# SensorBoard2.net
KiCad netlist of a schematic drawn in EAGLE
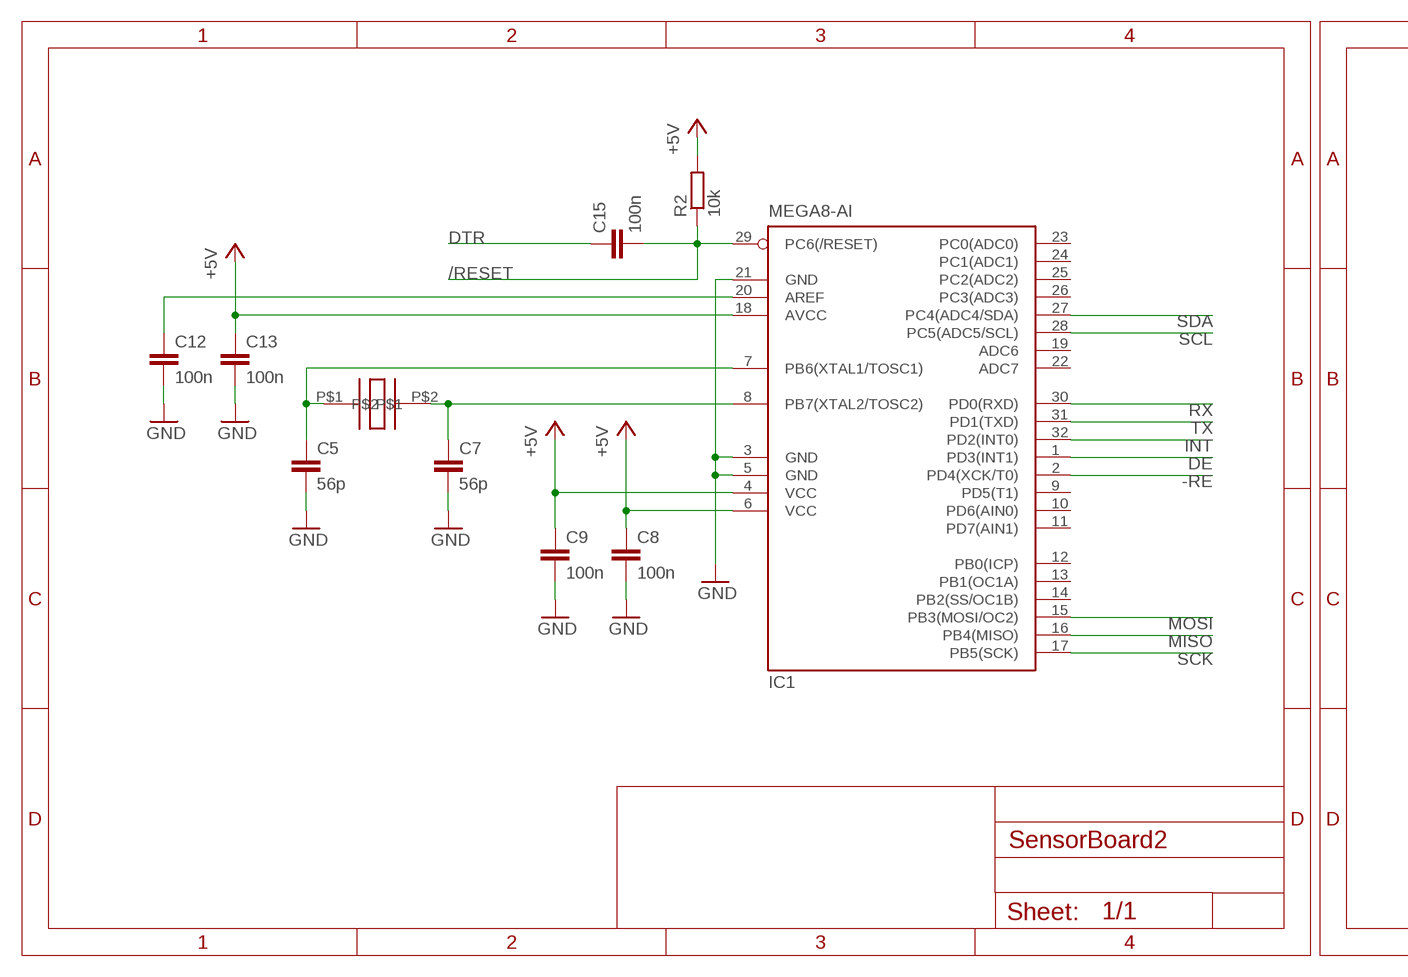
[diagram p0: schematic, sheet 1, part 1 of 2]
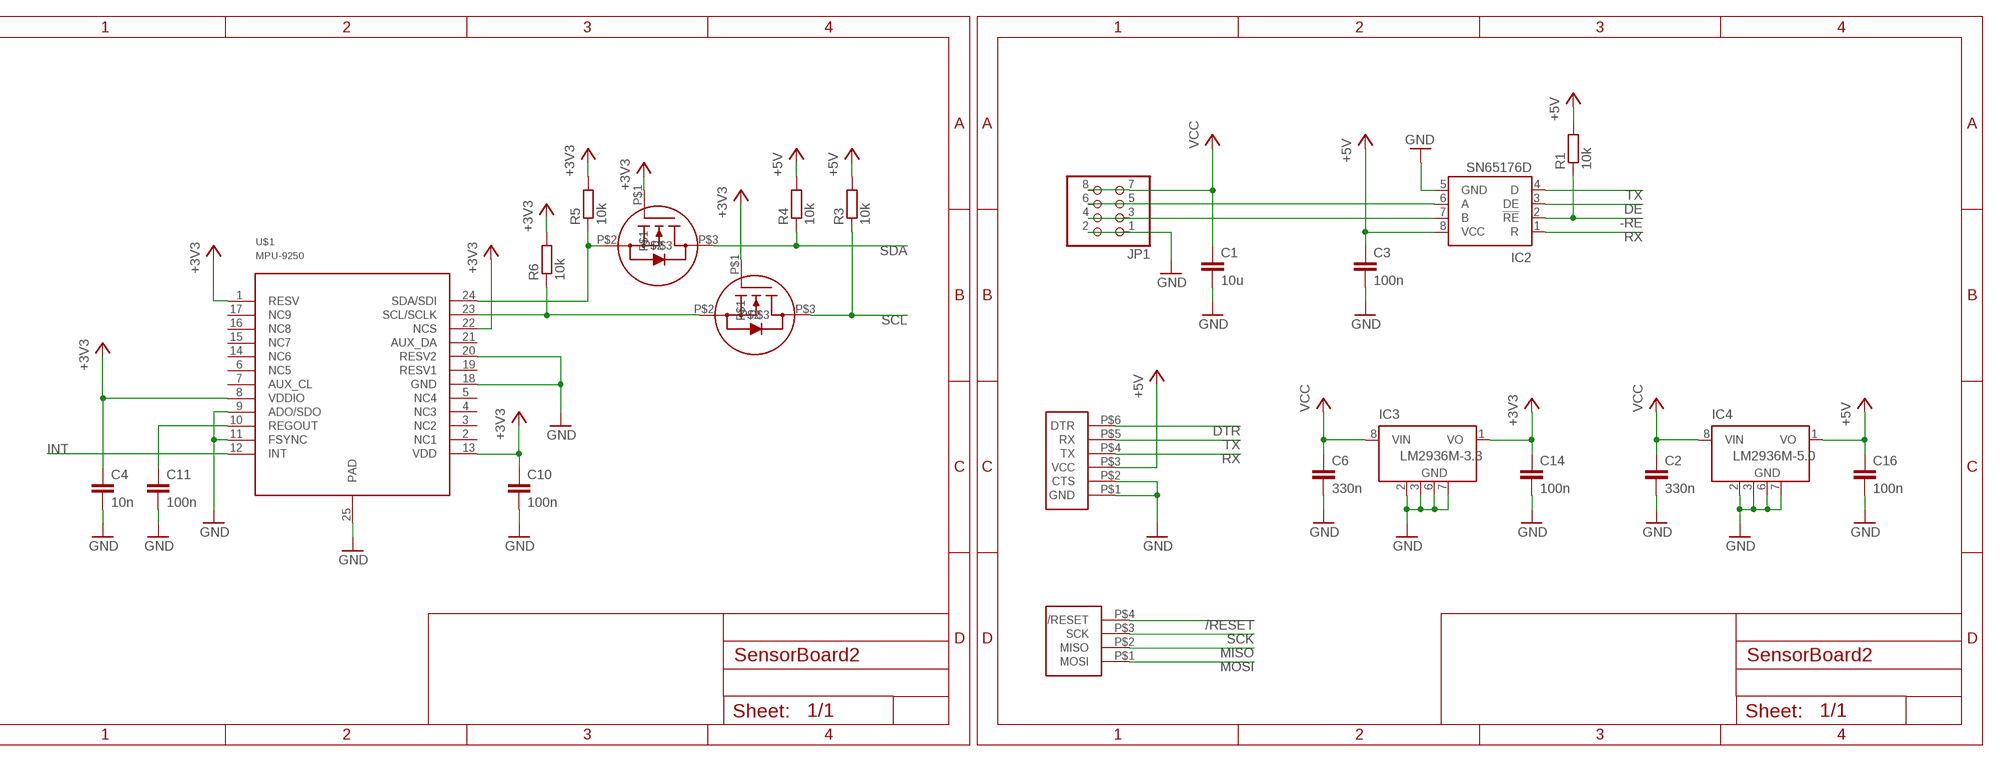
[diagram p1: schematic, sheet 1, part 2 of 2]

(export (version "E")
  (design (tool "Eeschema 10.0.6"))
  (components
    (comp (ref "C1")
      (value "10u")
      (footprint "eagle-import:C0805")
      (libsource (lib "eagle-import") (part "C-EUC0805"))
    )
    (comp (ref "C2")
      (value "330n")
      (footprint "eagle-import:C0603")
      (libsource (lib "eagle-import") (part "C-EUC0603"))
    )
    (comp (ref "C3")
      (value "100n")
      (footprint "eagle-import:C0603")
      (libsource (lib "eagle-import") (part "C-EUC0603"))
    )
    (comp (ref "C4")
      (value "10n")
      (footprint "eagle-import:C0603")
      (libsource (lib "eagle-import") (part "C-EUC0603"))
    )
    (comp (ref "C5")
      (value "56p")
      (footprint "eagle-import:C0603")
      (libsource (lib "eagle-import") (part "C-EUC0603"))
    )
    (comp (ref "C6")
      (value "330n")
      (footprint "eagle-import:C0603")
      (libsource (lib "eagle-import") (part "C-EUC0603"))
    )
    (comp (ref "C7")
      (value "56p")
      (footprint "eagle-import:C0603")
      (libsource (lib "eagle-import") (part "C-EUC0603"))
    )
    (comp (ref "C8")
      (value "100n")
      (footprint "eagle-import:C0603")
      (libsource (lib "eagle-import") (part "C-EUC0603"))
    )
    (comp (ref "C9")
      (value "100n")
      (footprint "eagle-import:C0603")
      (libsource (lib "eagle-import") (part "C-EUC0603"))
    )
    (comp (ref "C10")
      (value "100n")
      (footprint "eagle-import:C0603")
      (libsource (lib "eagle-import") (part "C-EUC0603"))
    )
    (comp (ref "C11")
      (value "100n")
      (footprint "eagle-import:C0603")
      (libsource (lib "eagle-import") (part "C-EUC0603"))
    )
    (comp (ref "C12")
      (value "100n")
      (footprint "eagle-import:C0603")
      (libsource (lib "eagle-import") (part "C-EUC0603"))
    )
    (comp (ref "C13")
      (value "100n")
      (footprint "eagle-import:C0603")
      (libsource (lib "eagle-import") (part "C-EUC0603"))
    )
    (comp (ref "C14")
      (value "100n")
      (footprint "eagle-import:C0603")
      (libsource (lib "eagle-import") (part "C-EUC0603"))
    )
    (comp (ref "C15")
      (value "100n")
      (footprint "eagle-import:C0603")
      (libsource (lib "eagle-import") (part "C-EUC0603"))
    )
    (comp (ref "C16")
      (value "100n")
      (footprint "eagle-import:C0603")
      (libsource (lib "eagle-import") (part "C-EUC0603"))
    )
    (comp (ref "IC1")
      (value "MEGA8-AI")
      (footprint "eagle-import:TQFP32-08")
      (fields (field (name "MPN") "ATMEGA8-16AU"))
      (libsource (lib "eagle-import") (part "MEGA8-AI"))
    )
    (comp (ref "IC2")
      (value "SN65176D")
      (footprint "eagle-import:SO-08")
      (fields (field (name "MF") "TEXAS INSTRUMENTS") (field (name "MPN") "SN65176BD"))
      (libsource (lib "eagle-import") (part "SN65176D"))
    )
    (comp (ref "IC3")
      (value "LM2936M-3.3")
      (footprint "eagle-import:SO08")
      (fields (field (name "MF") "NATIONAL SEMICONDUCTOR") (field (name "MPN") "LM2936M-3.3/NOPB"))
      (libsource (lib "eagle-import") (part "LM2936M?-3.3"))
    )
    (comp (ref "IC4")
      (value "LM2936M-5.0")
      (footprint "eagle-import:SO08")
      (fields (field (name "MF") "NATIONAL SEMICONDUCTOR") (field (name "MPN") "LM2936M-5.0/NOPB"))
      (libsource (lib "eagle-import") (part "LM2936M?-5.0"))
    )
    (comp (ref "JP1")
      (value "PINHD-2X4/90")
      (footprint "eagle-import:2X04_90")
      (libsource (lib "eagle-import") (part "PINHD-2X4/90"))
    )
    (comp (ref "R1")
      (value "10k")
      (footprint "eagle-import:R0603")
      (libsource (lib "eagle-import") (part "R-EU_R0603"))
    )
    (comp (ref "R2")
      (value "10k")
      (footprint "eagle-import:R0603")
      (libsource (lib "eagle-import") (part "R-EU_R0603"))
    )
    (comp (ref "R3")
      (value "10k")
      (footprint "eagle-import:R0603")
      (libsource (lib "eagle-import") (part "R-EU_R0603"))
    )
    (comp (ref "R4")
      (value "10k")
      (footprint "eagle-import:R0603")
      (libsource (lib "eagle-import") (part "R-EU_R0603"))
    )
    (comp (ref "R5")
      (value "10k")
      (footprint "eagle-import:R0603")
      (libsource (lib "eagle-import") (part "R-EU_R0603"))
    )
    (comp (ref "R6")
      (value "10k")
      (footprint "eagle-import:R0603")
      (libsource (lib "eagle-import") (part "R-EU_R0603"))
    )
    (comp (ref "U$1")
      (value "MPU-9250")
      (footprint "eagle-import:LEAD-QFN24")
      (libsource (lib "eagle-import") (part "MPU-9250"))
    )
    (comp (ref "U$2")
      (value "2N7002E")
      (footprint "eagle-import:SOT-23-3")
      (libsource (lib "eagle-import") (part "2N7002E"))
    )
    (comp (ref "U$3")
      (value "2N7002E")
      (footprint "eagle-import:SOT-23-3")
      (libsource (lib "eagle-import") (part "2N7002E"))
    )
    (comp (ref "U$4")
      (value "LFXTAL003240BULK")
      (footprint "eagle-import:LFXTAL003240BULK")
      (libsource (lib "eagle-import") (part "LFXTAL003240BULK"))
    )
    (comp (ref "U$5")
      (value "FTDI-PINHEADER")
      (footprint "eagle-import:FTDI-PINHEADER")
      (libsource (lib "eagle-import") (part "FTDI-PINHEADER"))
    )
    (comp (ref "U$6")
      (value "ISP_PADS")
      (footprint "eagle-import:ISP_PADS")
      (libsource (lib "eagle-import") (part "ISP_PADS"))
    )
  )
  (nets
    (net (code "1") (name "+3V3") (class "Default")
      (node (ref "C10") (pin "1") (pinfunction "1_1") (pintype "passive"))
      (node (ref "C14") (pin "1") (pinfunction "1_1") (pintype "passive"))
      (node (ref "C4") (pin "1") (pinfunction "1_1") (pintype "passive"))
      (node (ref "IC3") (pin "1") (pinfunction "VO_1") (pintype "passive"))
      (node (ref "R5") (pin "2") (pinfunction "2_2") (pintype "passive"))
      (node (ref "R6") (pin "2") (pinfunction "2_2") (pintype "passive"))
      (node (ref "U$1") (pin "1") (pinfunction "RESV_1") (pintype "bidirectional"))
      (node (ref "U$1") (pin "13") (pinfunction "VDD_13") (pintype "bidirectional"))
      (node (ref "U$1") (pin "22") (pinfunction "NCS_22") (pintype "bidirectional"))
      (node (ref "U$1") (pin "8") (pinfunction "VDDIO_8") (pintype "bidirectional"))
      (node (ref "U$2") (pin "P$1") (pinfunction "P$1_P$1") (pintype "bidirectional"))
      (node (ref "U$3") (pin "P$1") (pinfunction "P$1_P$1") (pintype "bidirectional"))
    )
    (net (code "2") (name "+5V") (class "Default")
      (node (ref "C13") (pin "1") (pinfunction "1_1") (pintype "passive"))
      (node (ref "C16") (pin "1") (pinfunction "1_1") (pintype "passive"))
      (node (ref "C3") (pin "1") (pinfunction "1_1") (pintype "passive"))
      (node (ref "C8") (pin "1") (pinfunction "1_1") (pintype "passive"))
      (node (ref "C9") (pin "1") (pinfunction "1_1") (pintype "passive"))
      (node (ref "IC1") (pin "18") (pinfunction "AVCC_18") (pintype "power_in"))
      (node (ref "IC1") (pin "4") (pinfunction "VCC_4") (pintype "power_in"))
      (node (ref "IC1") (pin "6") (pinfunction "VCC_6") (pintype "power_in"))
      (node (ref "IC2") (pin "8") (pinfunction "VCC_8") (pintype "input"))
      (node (ref "IC4") (pin "1") (pinfunction "VO_1") (pintype "passive"))
      (node (ref "R1") (pin "2") (pinfunction "2_2") (pintype "passive"))
      (node (ref "R2") (pin "2") (pinfunction "2_2") (pintype "passive"))
      (node (ref "R3") (pin "2") (pinfunction "2_2") (pintype "passive"))
      (node (ref "R4") (pin "2") (pinfunction "2_2") (pintype "passive"))
      (node (ref "U$5") (pin "P$3") (pinfunction "VCC_P$3") (pintype "bidirectional"))
    )
    (net (code "3") (name "/-RE") (class "Default")
      (node (ref "IC1") (pin "2") (pinfunction "PD4(XCK/T0)_2") (pintype "bidirectional"))
      (node (ref "IC2") (pin "2") (pinfunction "~{RE}_2") (pintype "input"))
      (node (ref "R1") (pin "1") (pinfunction "1_1") (pintype "passive"))
    )
    (net (code "4") (name "/DE") (class "Default")
      (node (ref "IC1") (pin "1") (pinfunction "PD3(INT1)_1") (pintype "bidirectional"))
      (node (ref "IC2") (pin "3") (pinfunction "DE_3") (pintype "input"))
    )
    (net (code "5") (name "/DTR") (class "Default")
      (node (ref "C15") (pin "1") (pinfunction "1_1") (pintype "passive"))
      (node (ref "U$5") (pin "P$6") (pinfunction "DTR_P$6") (pintype "bidirectional"))
    )
    (net (code "6") (name "/INT") (class "Default")
      (node (ref "IC1") (pin "32") (pinfunction "PD2(INT0)_32") (pintype "bidirectional"))
      (node (ref "U$1") (pin "12") (pinfunction "INT_12") (pintype "bidirectional"))
    )
    (net (code "7") (name "/MISO") (class "Default")
      (node (ref "IC1") (pin "16") (pinfunction "PB4(MISO)_16") (pintype "bidirectional"))
      (node (ref "U$6") (pin "P$2") (pinfunction "MISO_P$2") (pintype "bidirectional"))
    )
    (net (code "8") (name "/MOSI") (class "Default")
      (node (ref "IC1") (pin "15") (pinfunction "PB3(MOSI/OC2)_15") (pintype "bidirectional"))
      (node (ref "U$6") (pin "P$1") (pinfunction "MOSI_P$1") (pintype "bidirectional"))
    )
    (net (code "9") (name "/RX") (class "Default")
      (node (ref "IC1") (pin "30") (pinfunction "PD0(RXD)_30") (pintype "bidirectional"))
      (node (ref "IC2") (pin "1") (pinfunction "R_1") (pintype "input"))
      (node (ref "U$5") (pin "P$4") (pinfunction "TX_P$4") (pintype "bidirectional"))
    )
    (net (code "10") (name "/SCK") (class "Default")
      (node (ref "IC1") (pin "17") (pinfunction "PB5(SCK)_17") (pintype "bidirectional"))
      (node (ref "U$6") (pin "P$3") (pinfunction "SCK_P$3") (pintype "bidirectional"))
    )
    (net (code "11") (name "/SCL") (class "Default")
      (node (ref "IC1") (pin "28") (pinfunction "PC5(ADC5/SCL)_28") (pintype "bidirectional"))
      (node (ref "R3") (pin "1") (pinfunction "1_1") (pintype "passive"))
      (node (ref "U$2") (pin "P$3") (pinfunction "P$3_P$3") (pintype "bidirectional"))
    )
    (net (code "12") (name "/SDA") (class "Default")
      (node (ref "IC1") (pin "27") (pinfunction "PC4(ADC4/SDA)_27") (pintype "bidirectional"))
      (node (ref "R4") (pin "1") (pinfunction "1_1") (pintype "passive"))
      (node (ref "U$3") (pin "P$3") (pinfunction "P$3_P$3") (pintype "bidirectional"))
    )
    (net (code "13") (name "/TX") (class "Default")
      (node (ref "IC1") (pin "31") (pinfunction "PD1(TXD)_31") (pintype "bidirectional"))
      (node (ref "IC2") (pin "4") (pinfunction "D_4") (pintype "input"))
      (node (ref "U$5") (pin "P$5") (pinfunction "RX_P$5") (pintype "bidirectional"))
    )
    (net (code "14") (name "/{slash}RESET") (class "Default")
      (node (ref "C15") (pin "2") (pinfunction "2_2") (pintype "passive"))
      (node (ref "IC1") (pin "29") (pinfunction "PC6(/RESET)_29") (pintype "bidirectional"))
      (node (ref "R2") (pin "1") (pinfunction "1_1") (pintype "passive"))
      (node (ref "U$6") (pin "P$4") (pinfunction "/RESET_P$4") (pintype "bidirectional"))
    )
    (net (code "15") (name "GND") (class "Default")
      (node (ref "C1") (pin "2") (pinfunction "2_2") (pintype "passive"))
      (node (ref "C10") (pin "2") (pinfunction "2_2") (pintype "passive"))
      (node (ref "C11") (pin "2") (pinfunction "2_2") (pintype "passive"))
      (node (ref "C12") (pin "2") (pinfunction "2_2") (pintype "passive"))
      (node (ref "C13") (pin "2") (pinfunction "2_2") (pintype "passive"))
      (node (ref "C14") (pin "2") (pinfunction "2_2") (pintype "passive"))
      (node (ref "C16") (pin "2") (pinfunction "2_2") (pintype "passive"))
      (node (ref "C2") (pin "2") (pinfunction "2_2") (pintype "passive"))
      (node (ref "C3") (pin "2") (pinfunction "2_2") (pintype "passive"))
      (node (ref "C4") (pin "2") (pinfunction "2_2") (pintype "passive"))
      (node (ref "C5") (pin "2") (pinfunction "2_2") (pintype "passive"))
      (node (ref "C6") (pin "2") (pinfunction "2_2") (pintype "passive"))
      (node (ref "C7") (pin "2") (pinfunction "2_2") (pintype "passive"))
      (node (ref "C8") (pin "2") (pinfunction "2_2") (pintype "passive"))
      (node (ref "C9") (pin "2") (pinfunction "2_2") (pintype "passive"))
      (node (ref "IC1") (pin "21") (pinfunction "GND_21") (pintype "power_in"))
      (node (ref "IC1") (pin "3") (pinfunction "GND_3") (pintype "power_in"))
      (node (ref "IC1") (pin "5") (pinfunction "GND_5") (pintype "power_in"))
      (node (ref "IC2") (pin "5") (pinfunction "GND_5") (pintype "input"))
      (node (ref "IC3") (pin "2") (pinfunction "GND_2") (pintype "passive"))
      (node (ref "IC3") (pin "3") (pinfunction "GND_3") (pintype "passive"))
      (node (ref "IC3") (pin "6") (pinfunction "GND_6") (pintype "passive"))
      (node (ref "IC3") (pin "7") (pinfunction "GND_7") (pintype "passive"))
      (node (ref "IC4") (pin "2") (pinfunction "GND_2") (pintype "passive"))
      (node (ref "IC4") (pin "3") (pinfunction "GND_3") (pintype "passive"))
      (node (ref "IC4") (pin "6") (pinfunction "GND_6") (pintype "passive"))
      (node (ref "IC4") (pin "7") (pinfunction "GND_7") (pintype "passive"))
      (node (ref "JP1") (pin "1") (pinfunction "1_1") (pintype "passive"))
      (node (ref "JP1") (pin "2") (pinfunction "2_2") (pintype "passive"))
      (node (ref "U$1") (pin "11") (pinfunction "FSYNC_11") (pintype "bidirectional"))
      (node (ref "U$1") (pin "18") (pinfunction "GND_18") (pintype "bidirectional"))
      (node (ref "U$1") (pin "20") (pinfunction "RESV2_20") (pintype "bidirectional"))
      (node (ref "U$1") (pin "25") (pinfunction "PAD_25") (pintype "bidirectional"))
      (node (ref "U$1") (pin "9") (pinfunction "ADO/SDO_9") (pintype "bidirectional"))
      (node (ref "U$5") (pin "P$1") (pinfunction "GND_P$1") (pintype "bidirectional"))
      (node (ref "U$5") (pin "P$2") (pinfunction "CTS_P$2") (pintype "bidirectional"))
    )
    (net (code "16") (name "Net-(IC1-AREF)") (class "Default")
      (node (ref "C12") (pin "1") (pinfunction "1_1") (pintype "passive"))
      (node (ref "IC1") (pin "20") (pinfunction "AREF_20") (pintype "passive"))
    )
    (net (code "17") (name "Net-(IC1-PB6(XTAL1{slash}TOSC1))") (class "Default")
      (node (ref "C5") (pin "1") (pinfunction "1_1") (pintype "passive"))
      (node (ref "IC1") (pin "7") (pinfunction "PB6(XTAL1/TOSC1)_7") (pintype "bidirectional"))
      (node (ref "U$4") (pin "P$1") (pinfunction "P$1_P$1") (pintype "bidirectional"))
    )
    (net (code "18") (name "Net-(IC1-PB7(XTAL2{slash}TOSC2))") (class "Default")
      (node (ref "C7") (pin "1") (pinfunction "1_1") (pintype "passive"))
      (node (ref "IC1") (pin "8") (pinfunction "PB7(XTAL2/TOSC2)_8") (pintype "bidirectional"))
      (node (ref "U$4") (pin "P$2") (pinfunction "P$2_P$2") (pintype "bidirectional"))
    )
    (net (code "19") (name "Net-(IC2-A)") (class "Default")
      (node (ref "IC2") (pin "6") (pinfunction "A_6") (pintype "input"))
      (node (ref "JP1") (pin "5") (pinfunction "5_5") (pintype "passive"))
      (node (ref "JP1") (pin "6") (pinfunction "6_6") (pintype "passive"))
    )
    (net (code "20") (name "Net-(IC2-B)") (class "Default")
      (node (ref "IC2") (pin "7") (pinfunction "B_7") (pintype "input"))
      (node (ref "JP1") (pin "3") (pinfunction "3_3") (pintype "passive"))
      (node (ref "JP1") (pin "4") (pinfunction "4_4") (pintype "passive"))
    )
    (net (code "21") (name "Net-(U$1-REGOUT)") (class "Default")
      (node (ref "C11") (pin "1") (pinfunction "1_1") (pintype "passive"))
      (node (ref "U$1") (pin "10") (pinfunction "REGOUT_10") (pintype "bidirectional"))
    )
    (net (code "22") (name "Net-(U$1-SCL{slash}SCLK)") (class "Default")
      (node (ref "R6") (pin "1") (pinfunction "1_1") (pintype "passive"))
      (node (ref "U$1") (pin "23") (pinfunction "SCL/SCLK_23") (pintype "bidirectional"))
      (node (ref "U$2") (pin "P$2") (pinfunction "P$2_P$2") (pintype "bidirectional"))
    )
    (net (code "23") (name "Net-(U$1-SDA{slash}SDI)") (class "Default")
      (node (ref "R5") (pin "1") (pinfunction "1_1") (pintype "passive"))
      (node (ref "U$1") (pin "24") (pinfunction "SDA/SDI_24") (pintype "bidirectional"))
      (node (ref "U$3") (pin "P$2") (pinfunction "P$2_P$2") (pintype "bidirectional"))
    )
    (net (code "24") (name "VCC") (class "Default")
      (node (ref "C1") (pin "1") (pinfunction "1_1") (pintype "passive"))
      (node (ref "C2") (pin "1") (pinfunction "1_1") (pintype "passive"))
      (node (ref "C6") (pin "1") (pinfunction "1_1") (pintype "passive"))
      (node (ref "IC3") (pin "8") (pinfunction "VIN_8") (pintype "input"))
      (node (ref "IC4") (pin "8") (pinfunction "VIN_8") (pintype "input"))
      (node (ref "JP1") (pin "7") (pinfunction "7_7") (pintype "passive"))
      (node (ref "JP1") (pin "8") (pinfunction "8_8") (pintype "passive"))
    )
    (net (code "25") (name "unconnected-(IC1-ADC6-Pad19)") (class "Default")
      (node (ref "IC1") (pin "19") (pinfunction "ADC6_19") (pintype "bidirectional"))
    )
    (net (code "26") (name "unconnected-(IC1-ADC7-Pad22)") (class "Default")
      (node (ref "IC1") (pin "22") (pinfunction "ADC7_22") (pintype "bidirectional"))
    )
    (net (code "27") (name "unconnected-(IC1-PB0(ICP)-Pad12)") (class "Default")
      (node (ref "IC1") (pin "12") (pinfunction "PB0(ICP)_12") (pintype "bidirectional"))
    )
    (net (code "28") (name "unconnected-(IC1-PB1(OC1A)-Pad13)") (class "Default")
      (node (ref "IC1") (pin "13") (pinfunction "PB1(OC1A)_13") (pintype "bidirectional"))
    )
    (net (code "29") (name "unconnected-(IC1-PB2(SS{slash}OC1B)-Pad14)") (class "Default")
      (node (ref "IC1") (pin "14") (pinfunction "PB2(SS/OC1B)_14") (pintype "bidirectional"))
    )
    (net (code "30") (name "unconnected-(IC1-PC0(ADC0)-Pad23)") (class "Default")
      (node (ref "IC1") (pin "23") (pinfunction "PC0(ADC0)_23") (pintype "bidirectional"))
    )
    (net (code "31") (name "unconnected-(IC1-PC1(ADC1)-Pad24)") (class "Default")
      (node (ref "IC1") (pin "24") (pinfunction "PC1(ADC1)_24") (pintype "bidirectional"))
    )
    (net (code "32") (name "unconnected-(IC1-PC2(ADC2)-Pad25)") (class "Default")
      (node (ref "IC1") (pin "25") (pinfunction "PC2(ADC2)_25") (pintype "bidirectional"))
    )
    (net (code "33") (name "unconnected-(IC1-PC3(ADC3)-Pad26)") (class "Default")
      (node (ref "IC1") (pin "26") (pinfunction "PC3(ADC3)_26") (pintype "bidirectional"))
    )
    (net (code "34") (name "unconnected-(IC1-PD5(T1)-Pad9)") (class "Default")
      (node (ref "IC1") (pin "9") (pinfunction "PD5(T1)_9") (pintype "bidirectional"))
    )
    (net (code "35") (name "unconnected-(IC1-PD6(AIN0)-Pad10)") (class "Default")
      (node (ref "IC1") (pin "10") (pinfunction "PD6(AIN0)_10") (pintype "bidirectional"))
    )
    (net (code "36") (name "unconnected-(IC1-PD7(AIN1)-Pad11)") (class "Default")
      (node (ref "IC1") (pin "11") (pinfunction "PD7(AIN1)_11") (pintype "bidirectional"))
    )
    (net (code "37") (name "unconnected-(U$1-AUX_CL-Pad7)") (class "Default")
      (node (ref "U$1") (pin "7") (pinfunction "AUX_CL_7") (pintype "bidirectional"))
    )
    (net (code "38") (name "unconnected-(U$1-AUX_DA-Pad21)") (class "Default")
      (node (ref "U$1") (pin "21") (pinfunction "AUX_DA_21") (pintype "bidirectional"))
    )
    (net (code "39") (name "unconnected-(U$1-NC1-Pad2)") (class "Default")
      (node (ref "U$1") (pin "2") (pinfunction "NC1_2") (pintype "bidirectional"))
    )
    (net (code "40") (name "unconnected-(U$1-NC2-Pad3)") (class "Default")
      (node (ref "U$1") (pin "3") (pinfunction "NC2_3") (pintype "bidirectional"))
    )
    (net (code "41") (name "unconnected-(U$1-NC3-Pad4)") (class "Default")
      (node (ref "U$1") (pin "4") (pinfunction "NC3_4") (pintype "bidirectional"))
    )
    (net (code "42") (name "unconnected-(U$1-NC4-Pad5)") (class "Default")
      (node (ref "U$1") (pin "5") (pinfunction "NC4_5") (pintype "bidirectional"))
    )
    (net (code "43") (name "unconnected-(U$1-NC5-Pad6)") (class "Default")
      (node (ref "U$1") (pin "6") (pinfunction "NC5_6") (pintype "bidirectional"))
    )
    (net (code "44") (name "unconnected-(U$1-NC6-Pad14)") (class "Default")
      (node (ref "U$1") (pin "14") (pinfunction "NC6_14") (pintype "bidirectional"))
    )
    (net (code "45") (name "unconnected-(U$1-NC7-Pad15)") (class "Default")
      (node (ref "U$1") (pin "15") (pinfunction "NC7_15") (pintype "bidirectional"))
    )
    (net (code "46") (name "unconnected-(U$1-NC8-Pad16)") (class "Default")
      (node (ref "U$1") (pin "16") (pinfunction "NC8_16") (pintype "bidirectional"))
    )
    (net (code "47") (name "unconnected-(U$1-NC9-Pad17)") (class "Default")
      (node (ref "U$1") (pin "17") (pinfunction "NC9_17") (pintype "bidirectional"))
    )
    (net (code "48") (name "unconnected-(U$1-RESV1-Pad19)") (class "Default")
      (node (ref "U$1") (pin "19") (pinfunction "RESV1_19") (pintype "bidirectional"))
    )
  )
)
